# SSTuino_Evo.net
KiCad netlist of a schematic drawn in EAGLE
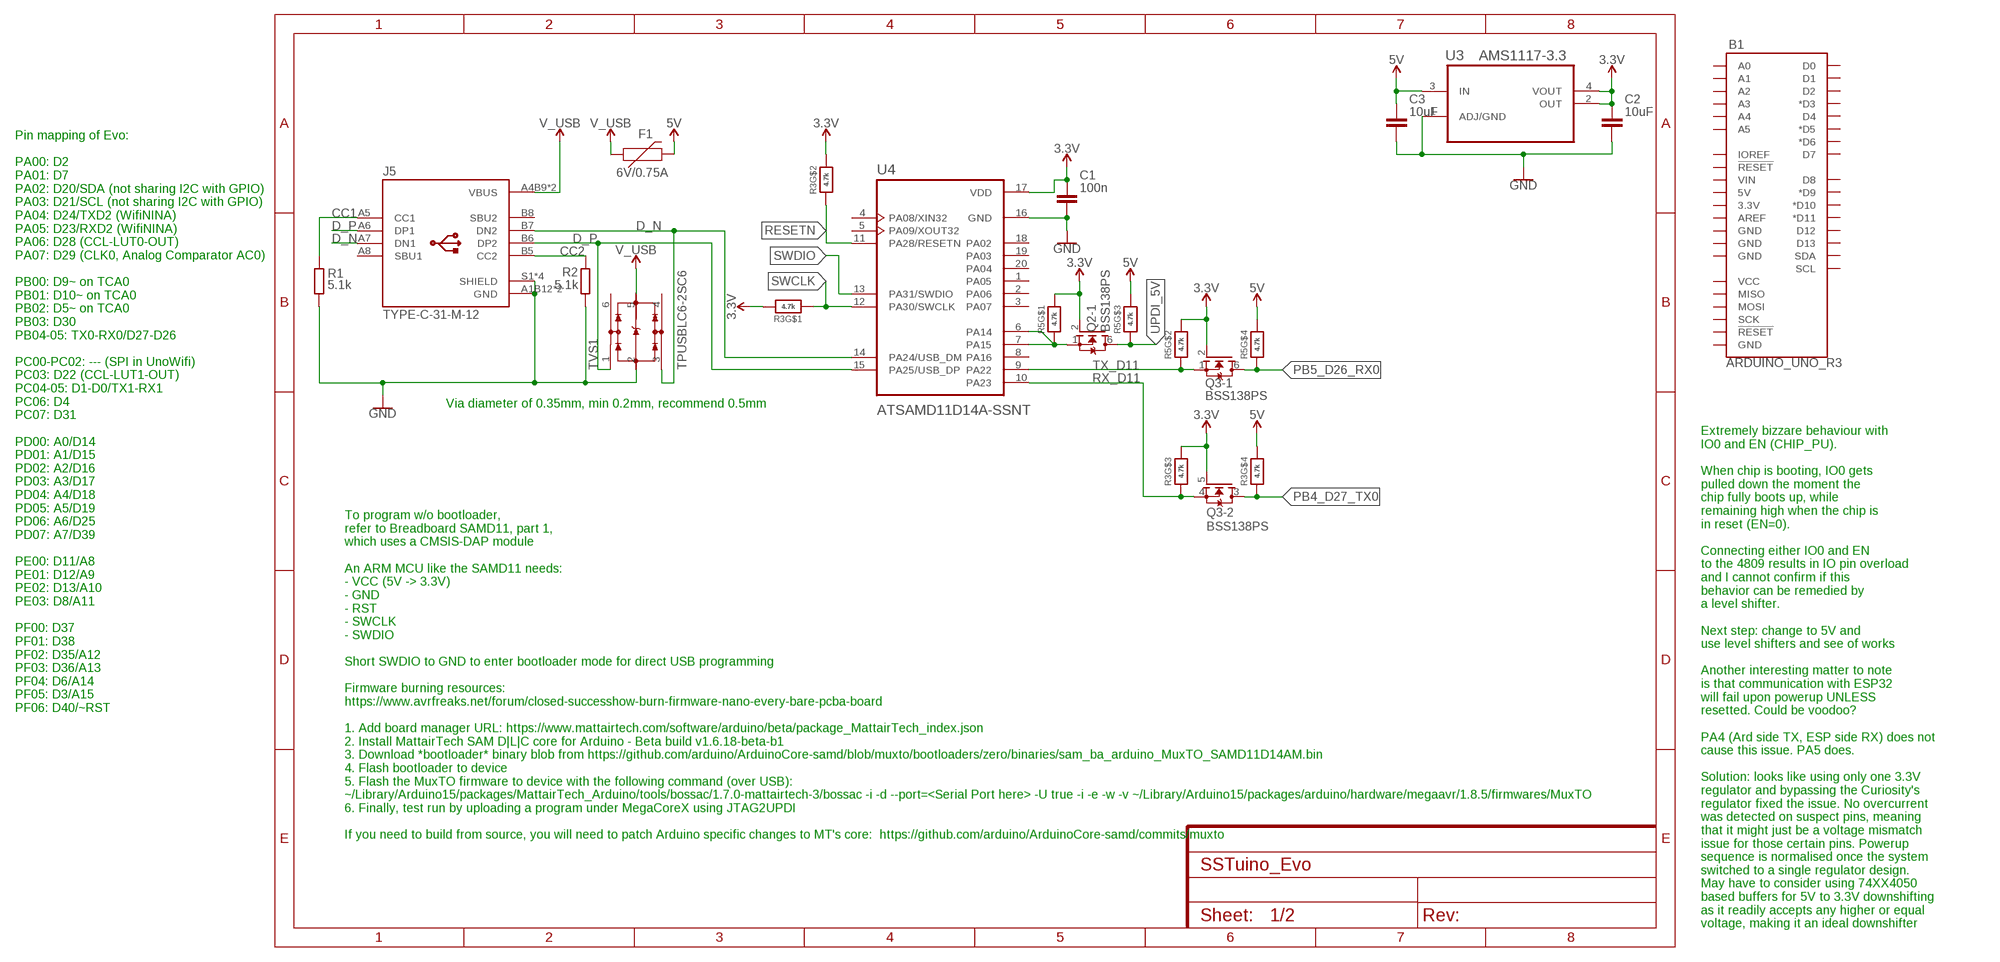
[diagram p0: schematic, sheet 1]
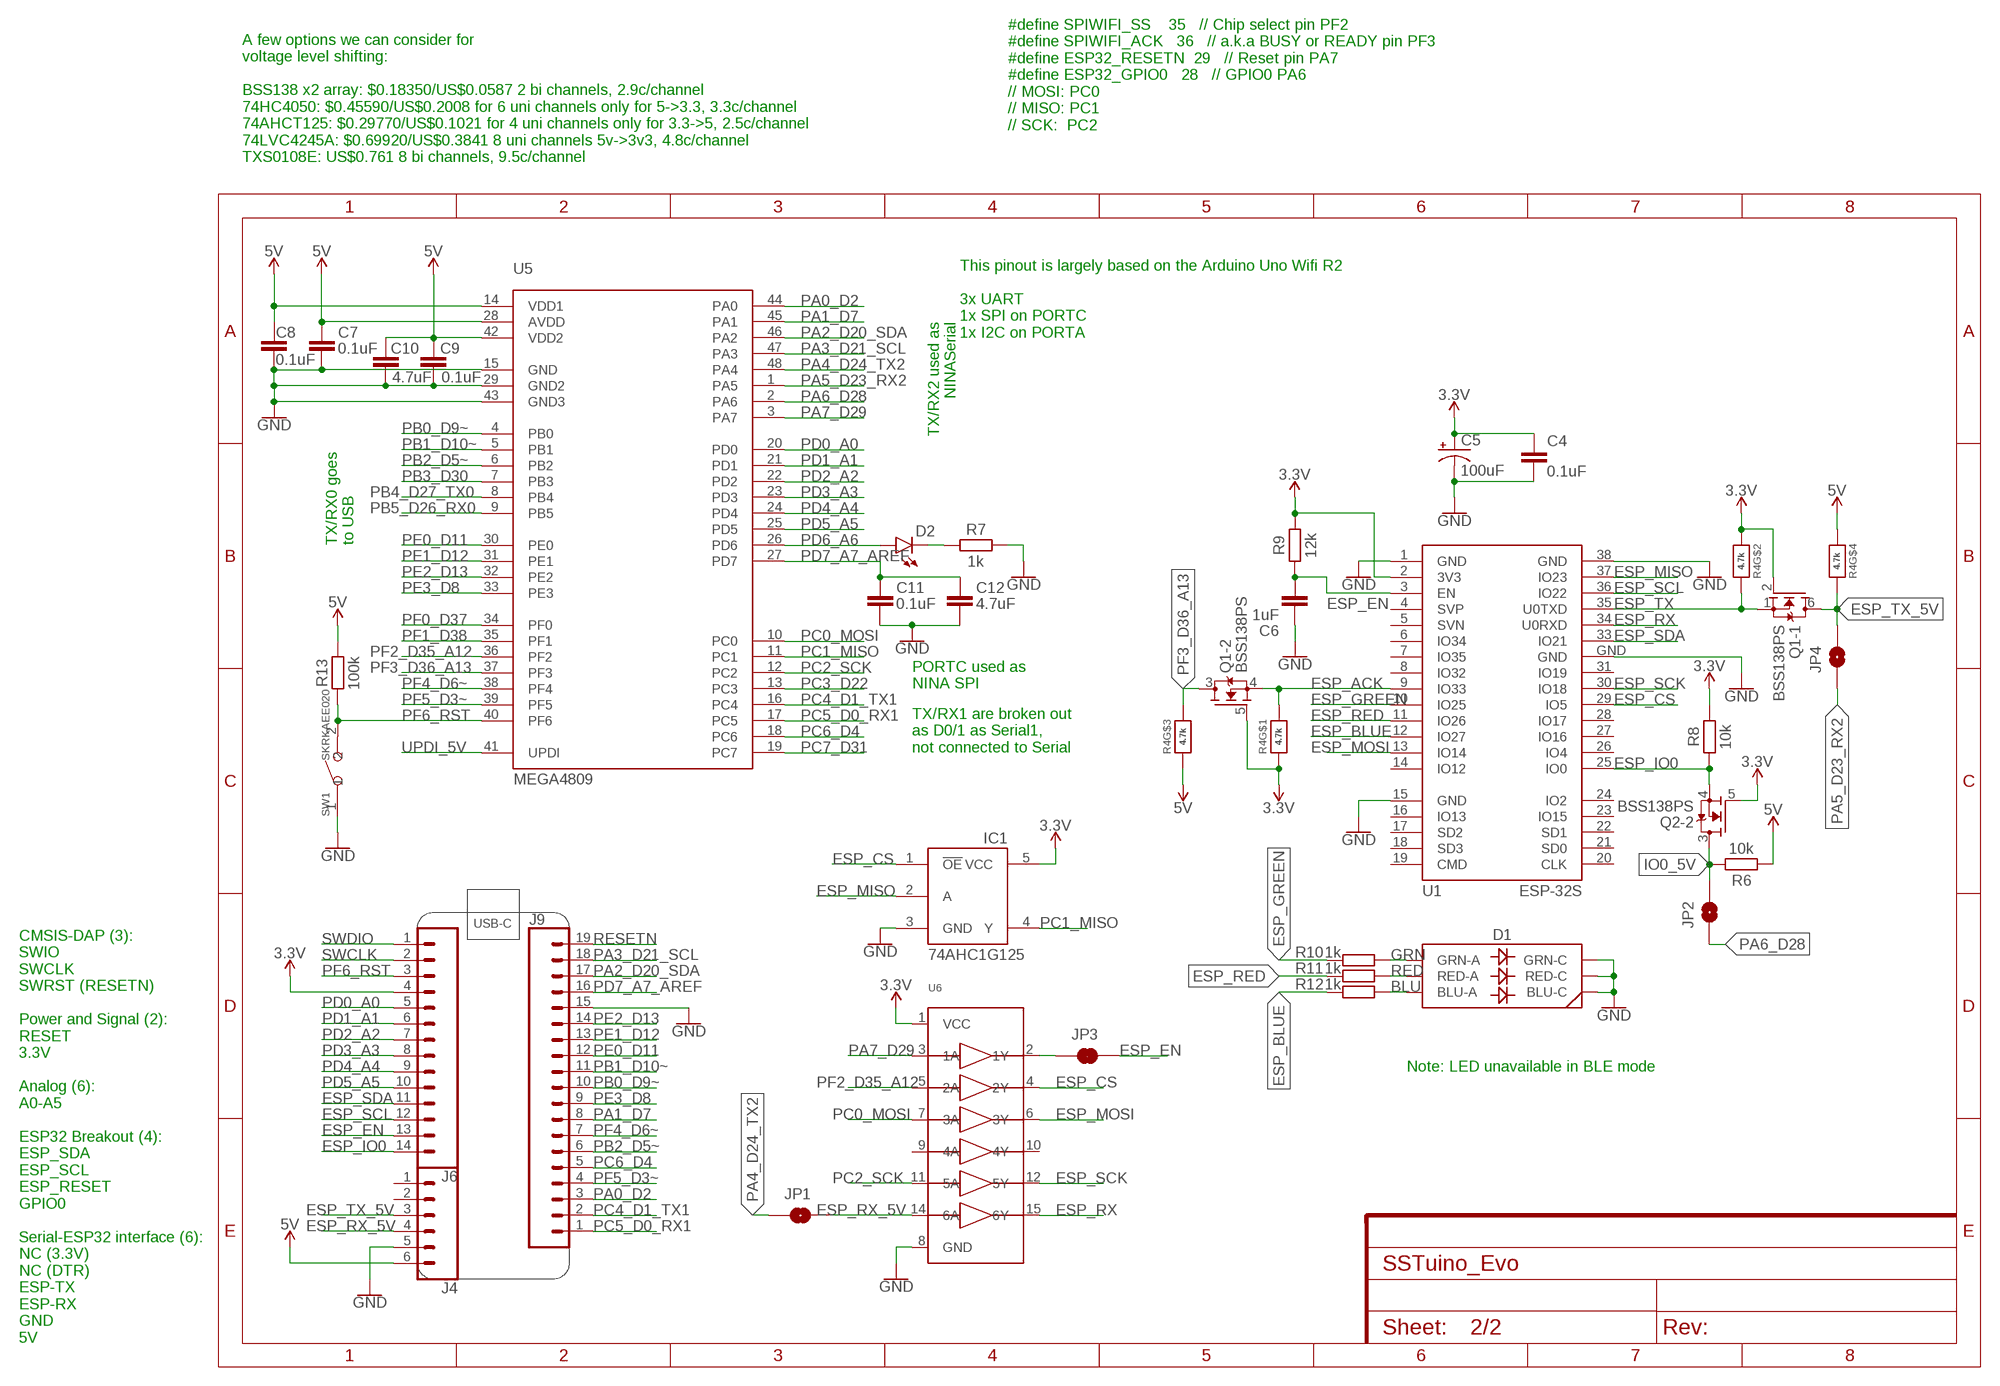
[diagram p1: schematic, sheet 2]

(export (version "E")
  (design (tool "Eeschema 10.0.6"))
  (components
    (comp (ref "C4")
      (value "0.1uF")
      (footprint "eagle-import:CAPC1005X60")
      (libsource (lib "eagle-import") (part "CCHIP-0402(1005-METRIC)_"))
    )
    (comp (ref "C5")
      (value "100uF")
      (footprint "eagle-import:CAPMP3216X180N")
      (libsource (lib "eagle-import") (part "C-POL-USTANTALUM-1206(3216-METRIC)_"))
    )
    (comp (ref "C6")
      (value "1uF")
      (footprint "eagle-import:CAPC1005X60")
      (libsource (lib "eagle-import") (part "CCHIP-0402(1005-METRIC)_"))
    )
    (comp (ref "C7")
      (value "0.1uF")
      (footprint "eagle-import:CAPC1005X60")
      (libsource (lib "eagle-import") (part "CCHIP-0402(1005-METRIC)_"))
    )
    (comp (ref "C8")
      (value "0.1uF")
      (footprint "eagle-import:CAPC1005X60")
      (libsource (lib "eagle-import") (part "CCHIP-0402(1005-METRIC)_"))
    )
    (comp (ref "C9")
      (value "0.1uF")
      (footprint "eagle-import:CAPC1005X60")
      (libsource (lib "eagle-import") (part "CCHIP-0402(1005-METRIC)_"))
    )
    (comp (ref "C10")
      (value "4.7uF")
      (footprint "eagle-import:CAPC1005X60")
      (libsource (lib "eagle-import") (part "CCHIP-0402(1005-METRIC)_"))
    )
    (comp (ref "C11")
      (value "0.1uF")
      (footprint "eagle-import:CAPC1005X60")
      (libsource (lib "eagle-import") (part "CCHIP-0402(1005-METRIC)_"))
    )
    (comp (ref "C12")
      (value "4.7uF")
      (footprint "eagle-import:CAPC1005X60")
      (libsource (lib "eagle-import") (part "CCHIP-0402(1005-METRIC)_"))
    )
    (comp (ref "D1")
      (value "LED-RGBTC5050RGBF08")
      (footprint "eagle-import:LED-TRICOLOR-5050")
      (libsource (lib "eagle-import") (part "LED-RGBTC5050RGBF08"))
    )
    (comp (ref "D2")
      (value "LED0603")
      (footprint "eagle-import:LED-0603")
      (libsource (lib "eagle-import") (part "LED0603"))
    )
    (comp (ref "IC1")
      (value "74AHC1G125")
      (footprint "eagle-import:SOT23-5L")
      (fields (field (name "LCSC_PART") "C124295"))
      (libsource (lib "eagle-import") (part "74AHC1G125"))
    )
    (comp (ref "J4")
      (value "CONN_06NO_SILK_FEMALE_PTH")
      (footprint "eagle-import:1X06_NO_SILK")
      (libsource (lib "eagle-import") (part "CONN_06NO_SILK_FEMALE_PTH"))
    )
    (comp (ref "J6")
      (value "CONN_14NO_SILK")
      (footprint "eagle-import:1X14_NO_SILK")
      (libsource (lib "eagle-import") (part "CONN_14NO_SILK"))
    )
    (comp (ref "J9")
      (value "CONN_191X19_NO_SILK")
      (footprint "eagle-import:1X19_NO_SILK")
      (libsource (lib "eagle-import") (part "CONN_191X19_NO_SILK"))
    )
    (comp (ref "JP1")
      (value "JUMPER-SMT_2_NO_SILK")
      (footprint "eagle-import:SMT-JUMPER_2_NO_SILK")
      (libsource (lib "eagle-import") (part "JUMPER-SMT_2_NO_SILK"))
    )
    (comp (ref "JP2")
      (value "JUMPER-SMT_2_NO_SILK")
      (footprint "eagle-import:SMT-JUMPER_2_NO_SILK")
      (libsource (lib "eagle-import") (part "JUMPER-SMT_2_NO_SILK"))
    )
    (comp (ref "JP3")
      (value "JUMPER-SMT_2_NC_TRACE_SILK")
      (footprint "eagle-import:SMT-JUMPER_2_NC_TRACE_SILK")
      (libsource (lib "eagle-import") (part "JUMPER-SMT_2_NC_TRACE_SILK"))
    )
    (comp (ref "JP4")
      (value "JUMPER-SMT_2_NO_SILK")
      (footprint "eagle-import:SMT-JUMPER_2_NO_SILK")
      (libsource (lib "eagle-import") (part "JUMPER-SMT_2_NO_SILK"))
    )
    (comp (ref "Q1")
      (value "BSS138PS")
      (footprint "eagle-import:ARDUINO-TRANSISTORS_SOT363")
      (fields (field (name "MANUFACTURER") "NXP") (field (name "LCSC_PART") "C193381"))
      (libsource (lib "eagle-import") (part "BSS138PS"))
    )
    (comp (ref "Q2")
      (value "BSS138PS")
      (footprint "eagle-import:ARDUINO-TRANSISTORS_SOT363")
      (fields (field (name "MANUFACTURER") "NXP") (field (name "LCSC_PART") "C193381"))
      (libsource (lib "eagle-import") (part "BSS138PS"))
    )
    (comp (ref "R4")
      (value "4.7k")
      (footprint "eagle-import:RESPACK_4X0402")
      (fields (field (name "LCSC_PART") "C1980"))
      (libsource (lib "eagle-import") (part "RESISTOR_4PACK0402"))
    )
    (comp (ref "R6")
      (value "10k")
      (footprint "eagle-import:RESC1005X40")
      (libsource (lib "eagle-import") (part "RCHIP-0402(1005-METRIC)_"))
    )
    (comp (ref "R7")
      (value "1k")
      (footprint "eagle-import:RESC1005X40")
      (libsource (lib "eagle-import") (part "RCHIP-0402(1005-METRIC)_"))
    )
    (comp (ref "R8")
      (value "10k")
      (footprint "eagle-import:RESC1005X40")
      (libsource (lib "eagle-import") (part "RCHIP-0402(1005-METRIC)_"))
    )
    (comp (ref "R9")
      (value "12k")
      (footprint "eagle-import:RESC1005X40")
      (libsource (lib "eagle-import") (part "RCHIP-0402(1005-METRIC)_"))
    )
    (comp (ref "R10")
      (value "1k")
      (footprint "eagle-import:RESC1005X40")
      (libsource (lib "eagle-import") (part "RCHIP-0402(1005-METRIC)_"))
    )
    (comp (ref "R11")
      (value "1k")
      (footprint "eagle-import:RESC1005X40")
      (libsource (lib "eagle-import") (part "RCHIP-0402(1005-METRIC)_"))
    )
    (comp (ref "R12")
      (value "1k")
      (footprint "eagle-import:RESC1005X40")
      (libsource (lib "eagle-import") (part "RCHIP-0402(1005-METRIC)_"))
    )
    (comp (ref "R13")
      (value "100k")
      (footprint "eagle-import:RESC1005X40")
      (libsource (lib "eagle-import") (part "RCHIP-0402(1005-METRIC)_"))
    )
    (comp (ref "SW1")
      (value "SKRKAEE020")
      (footprint "eagle-import:SW2-2.6-3.9X2.9X1.5+0.4MM")
      (fields (field (name "LCSC_PART") "C115357") (field (name "LCSC_PART_1") "C115357"))
      (libsource (lib "eagle-import") (part "SMD-BUTTON(2P-3.9X2.9X1.5+0.4MM)-SKRKAEE020"))
    )
    (comp (ref "U1")
      (value "ESP-32S")
      (footprint "eagle-import:ESP-32S")
      (libsource (lib "eagle-import") (part "ESP-32S"))
    )
    (comp (ref "U5")
      (value "MEGA4809")
      (footprint "eagle-import:TQFP48")
      (fields (field (name "LCSC_PART") "C189475"))
      (libsource (lib "eagle-import") (part "MEGA4809"))
    )
    (comp (ref "U6")
      (value "74HC4050DTSSOP")
      (footprint "eagle-import:TSSOP16")
      (fields (field (name "LCSC_PART") "C43181"))
      (libsource (lib "eagle-import") (part "74HC4050DTSSOP"))
    )
    (comp (ref "B1")
      (value "ARDUINO_UNO_R3")
      (footprint "eagle-import:ARDUINO_R3")
      (libsource (lib "eagle-import") (part "ARDUINO_UNO_R3"))
    )
    (comp (ref "C1")
      (value "100n")
      (footprint "eagle-import:CAPC1005X60")
      (libsource (lib "eagle-import") (part "CCHIP-0402(1005-METRIC)_"))
    )
    (comp (ref "C2")
      (value "10uF")
      (footprint "eagle-import:CAPC1608X85")
      (libsource (lib "eagle-import") (part "CCHIP-0603(1608-METRIC)_"))
    )
    (comp (ref "C3")
      (value "10uF")
      (footprint "eagle-import:CAPC1608X85")
      (libsource (lib "eagle-import") (part "CCHIP-0603(1608-METRIC)_"))
    )
    (comp (ref "F1")
      (value "6V/0.75A")
      (footprint "eagle-import:1206")
      (fields (field (name "LCSC_PART") "C99563"))
      (libsource (lib "eagle-import") (part "PPTC_THREE-QUARTER-AMP"))
    )
    (comp (ref "J5")
      (value "TYPE-C-31-M-12")
      (footprint "eagle-import:HRO_TYPE-C-31-M-12")
      (fields (field (name "MF") "HRO Electronics Co., Ltd.") (field (name "LCSC_PART") "C165948"))
      (libsource (lib "eagle-import") (part "TYPE-C-31-M-12"))
    )
    (comp (ref "Q3")
      (value "BSS138PS")
      (footprint "eagle-import:ARDUINO-TRANSISTORS_SOT363")
      (fields (field (name "MANUFACTURER") "NXP") (field (name "LCSC_PART") "C193381"))
      (libsource (lib "eagle-import") (part "BSS138PS"))
    )
    (comp (ref "R1")
      (value "5.1k")
      (footprint "eagle-import:RESC1005X40")
      (libsource (lib "eagle-import") (part "RCHIP-0402(1005-METRIC)_"))
    )
    (comp (ref "R2")
      (value "5.1k")
      (footprint "eagle-import:RESC1005X40")
      (libsource (lib "eagle-import") (part "RCHIP-0402(1005-METRIC)_"))
    )
    (comp (ref "R3")
      (value "4.7k")
      (footprint "eagle-import:RESPACK_4X0402")
      (fields (field (name "LCSC_PART") "C1980"))
      (libsource (lib "eagle-import") (part "RESISTOR_4PACK0402"))
    )
    (comp (ref "R5")
      (value "4.7k")
      (footprint "eagle-import:RESPACK_4X0402")
      (fields (field (name "LCSC_PART") "C1980"))
      (libsource (lib "eagle-import") (part "RESISTOR_4PACK0402"))
    )
    (comp (ref "TVS1")
      (value "TPUSBLC6-2SC6")
      (footprint "eagle-import:SOT95P280X110-6N")
      (fields (field (name "LCSC_PART") "C558442"))
      (libsource (lib "eagle-import") (part "TPUSBLC6-2SC6"))
    )
    (comp (ref "U3")
      (value "AMS1117-3.3")
      (footprint "eagle-import:SOT230P696X180-4N")
      (fields (field (name "MPN") "LM1117MP-3.3") (field (name "LCSC_PART") "C6186"))
      (libsource (lib "eagle-import") (part "LM1117MP-3.3"))
    )
    (comp (ref "U4")
      (value "ATSAMD11D14A-SSNT")
      (footprint "eagle-import:SOIC127P1030X265-20N")
      (fields (field (name "MF") "Microchip") (field (name "LCSC_PART") "C2053599"))
      (libsource (lib "eagle-import") (part "ATSAMD11D14A-SSNT"))
    )
  )
  (nets
    (net (code "1") (name "3.3V") (class "Default")
      (node (ref "C1") (pin "1") (pinfunction "1_1") (pintype "passive"))
      (node (ref "C2") (pin "1") (pinfunction "1_1") (pintype "passive"))
      (node (ref "C4") (pin "1") (pinfunction "1_1") (pintype "passive"))
      (node (ref "C5") (pin "1") (pinfunction "+_1") (pintype "passive"))
      (node (ref "IC1") (pin "5") (pinfunction "VCC_5") (pintype "power_in"))
      (node (ref "J6") (pin "4") (pinfunction "4_4") (pintype "passive"))
      (node (ref "Q1") (pin "2") (pinfunction "G_2") (pintype "passive"))
      (node (ref "Q1") (pin "5") (pinfunction "G_5") (pintype "passive"))
      (node (ref "Q2") (pin "2") (pinfunction "G_2") (pintype "passive"))
      (node (ref "Q2") (pin "5") (pinfunction "G_5") (pintype "passive"))
      (node (ref "Q3") (pin "2") (pinfunction "G_2") (pintype "passive"))
      (node (ref "Q3") (pin "5") (pinfunction "G_5") (pintype "passive"))
      (node (ref "R3") (pin "6") (pinfunction "2_6") (pintype "passive"))
      (node (ref "R3") (pin "7") (pinfunction "2_7") (pintype "passive"))
      (node (ref "R3") (pin "8") (pinfunction "2_8") (pintype "passive"))
      (node (ref "R4") (pin "1") (pinfunction "1_1") (pintype "passive"))
      (node (ref "R4") (pin "2") (pinfunction "1_2") (pintype "passive"))
      (node (ref "R5") (pin "7") (pinfunction "2_7") (pintype "passive"))
      (node (ref "R5") (pin "8") (pinfunction "2_8") (pintype "passive"))
      (node (ref "R8") (pin "2") (pinfunction "2_2") (pintype "passive"))
      (node (ref "R9") (pin "2") (pinfunction "2_2") (pintype "passive"))
      (node (ref "U1") (pin "2") (pinfunction "3V3_2") (pintype "power_in"))
      (node (ref "U3") (pin "2") (pinfunction "OUT_2") (pintype "output"))
      (node (ref "U3") (pin "4") (pinfunction "VOUT_4") (pintype "output"))
      (node (ref "U4") (pin "17") (pinfunction "VDD_17") (pintype "power_in"))
      (node (ref "U6") (pin "1") (pinfunction "VCC_1") (pintype "bidirectional"))
    )
    (net (code "2") (name "5V") (class "Default")
      (node (ref "C10") (pin "1") (pinfunction "1_1") (pintype "passive"))
      (node (ref "C3") (pin "1") (pinfunction "1_1") (pintype "passive"))
      (node (ref "C7") (pin "1") (pinfunction "1_1") (pintype "passive"))
      (node (ref "C8") (pin "1") (pinfunction "1_1") (pintype "passive"))
      (node (ref "C9") (pin "1") (pinfunction "1_1") (pintype "passive"))
      (node (ref "F1") (pin "2") (pinfunction "2_2") (pintype "bidirectional"))
      (node (ref "J4") (pin "6") (pinfunction "6_6") (pintype "passive"))
      (node (ref "R13") (pin "2") (pinfunction "2_2") (pintype "passive"))
      (node (ref "R3") (pin "5") (pinfunction "2_5") (pintype "passive"))
      (node (ref "R4") (pin "3") (pinfunction "1_3") (pintype "passive"))
      (node (ref "R4") (pin "4") (pinfunction "1_4") (pintype "passive"))
      (node (ref "R5") (pin "5") (pinfunction "2_5") (pintype "passive"))
      (node (ref "R5") (pin "6") (pinfunction "2_6") (pintype "passive"))
      (node (ref "R6") (pin "1") (pinfunction "1_1") (pintype "passive"))
      (node (ref "U3") (pin "3") (pinfunction "IN_3") (pintype "input"))
      (node (ref "U5") (pin "14") (pinfunction "VDD1_14") (pintype "bidirectional"))
      (node (ref "U5") (pin "28") (pinfunction "AVDD_28") (pintype "bidirectional"))
      (node (ref "U5") (pin "42") (pinfunction "VDD2_42") (pintype "bidirectional"))
    )
    (net (code "3") (name "BLU") (class "Default")
      (node (ref "D1") (pin "6") (pinfunction "BLU-A_6") (pintype "bidirectional"))
      (node (ref "R12") (pin "2") (pinfunction "2_2") (pintype "passive"))
    )
    (net (code "4") (name "CC1") (class "Default")
      (node (ref "J5") (pin "A5") (pinfunction "CC1_A5") (pintype "bidirectional"))
      (node (ref "R1") (pin "1") (pinfunction "1_1") (pintype "passive"))
    )
    (net (code "5") (name "CC2") (class "Default")
      (node (ref "J5") (pin "B5") (pinfunction "CC2_B5") (pintype "bidirectional"))
      (node (ref "R2") (pin "2") (pinfunction "2_2") (pintype "passive"))
    )
    (net (code "6") (name "D_N") (class "Default")
      (node (ref "J5") (pin "A7") (pinfunction "DN1_A7") (pintype "bidirectional"))
      (node (ref "J5") (pin "B7") (pinfunction "DN2_B7") (pintype "bidirectional"))
      (node (ref "TVS1") (pin "3") (pinfunction "IO2_3") (pintype "passive"))
      (node (ref "U4") (pin "14") (pinfunction "PA24/USB_DM_14") (pintype "bidirectional"))
    )
    (net (code "7") (name "D_P") (class "Default")
      (node (ref "J5") (pin "A6") (pinfunction "DP1_A6") (pintype "bidirectional"))
      (node (ref "J5") (pin "B6") (pinfunction "DP2_B6") (pintype "bidirectional"))
      (node (ref "TVS1") (pin "1") (pinfunction "IO1_1") (pintype "passive"))
      (node (ref "U4") (pin "15") (pinfunction "PA25/USB_DP_15") (pintype "bidirectional"))
    )
    (net (code "8") (name "ESP_ACK") (class "Default")
      (node (ref "Q1") (pin "4") (pinfunction "S_4") (pintype "passive"))
      (node (ref "R4") (pin "8") (pinfunction "2_8") (pintype "passive"))
      (node (ref "U1") (pin "9") (pinfunction "IO33_9") (pintype "bidirectional"))
    )
    (net (code "9") (name "ESP_BLUE") (class "Default")
      (node (ref "R12") (pin "1") (pinfunction "1_1") (pintype "passive"))
      (node (ref "U1") (pin "12") (pinfunction "IO27_12") (pintype "bidirectional"))
    )
    (net (code "10") (name "ESP_CS") (class "Default")
      (node (ref "IC1") (pin "1") (pinfunction "~{OE}_1") (pintype "input"))
      (node (ref "U1") (pin "29") (pinfunction "IO5_29") (pintype "bidirectional"))
      (node (ref "U6") (pin "4") (pinfunction "2Y_4") (pintype "bidirectional"))
    )
    (net (code "11") (name "ESP_EN") (class "Default")
      (node (ref "C6") (pin "2") (pinfunction "2_2") (pintype "passive"))
      (node (ref "J6") (pin "13") (pinfunction "13_13") (pintype "passive"))
      (node (ref "JP3") (pin "2") (pinfunction "2_2") (pintype "passive"))
      (node (ref "R9") (pin "1") (pinfunction "1_1") (pintype "passive"))
      (node (ref "U1") (pin "3") (pinfunction "EN_3") (pintype "input"))
    )
    (net (code "12") (name "ESP_GREEN") (class "Default")
      (node (ref "R10") (pin "1") (pinfunction "1_1") (pintype "passive"))
      (node (ref "U1") (pin "10") (pinfunction "IO25_10") (pintype "bidirectional"))
    )
    (net (code "13") (name "ESP_IO0") (class "Default")
      (node (ref "J6") (pin "14") (pinfunction "14_14") (pintype "passive"))
      (node (ref "Q2") (pin "4") (pinfunction "S_4") (pintype "passive"))
      (node (ref "R8") (pin "1") (pinfunction "1_1") (pintype "passive"))
      (node (ref "U1") (pin "25") (pinfunction "IO0_25") (pintype "bidirectional"))
    )
    (net (code "14") (name "ESP_MISO") (class "Default")
      (node (ref "IC1") (pin "2") (pinfunction "A_2") (pintype "input"))
      (node (ref "U1") (pin "37") (pinfunction "IO23_37") (pintype "bidirectional"))
    )
    (net (code "15") (name "ESP_MOSI") (class "Default")
      (node (ref "U1") (pin "13") (pinfunction "IO14_13") (pintype "bidirectional"))
      (node (ref "U6") (pin "6") (pinfunction "3Y_6") (pintype "bidirectional"))
    )
    (net (code "16") (name "ESP_RED") (class "Default")
      (node (ref "R11") (pin "1") (pinfunction "1_1") (pintype "passive"))
      (node (ref "U1") (pin "11") (pinfunction "IO26_11") (pintype "bidirectional"))
    )
    (net (code "17") (name "ESP_RX") (class "Default")
      (node (ref "U1") (pin "34") (pinfunction "U0RXD_34") (pintype "bidirectional"))
      (node (ref "U6") (pin "15") (pinfunction "6Y_15") (pintype "bidirectional"))
    )
    (net (code "18") (name "ESP_RX_5V") (class "Default")
      (node (ref "J4") (pin "4") (pinfunction "4_4") (pintype "passive"))
      (node (ref "JP1") (pin "2") (pinfunction "2_2") (pintype "passive"))
      (node (ref "U6") (pin "14") (pinfunction "6A_14") (pintype "bidirectional"))
    )
    (net (code "19") (name "ESP_SCK") (class "Default")
      (node (ref "U1") (pin "30") (pinfunction "IO18_30") (pintype "bidirectional"))
      (node (ref "U6") (pin "12") (pinfunction "5Y_12") (pintype "bidirectional"))
    )
    (net (code "20") (name "ESP_SCL") (class "Default")
      (node (ref "J6") (pin "12") (pinfunction "12_12") (pintype "passive"))
      (node (ref "U1") (pin "36") (pinfunction "IO22_36") (pintype "bidirectional"))
    )
    (net (code "21") (name "ESP_SDA") (class "Default")
      (node (ref "J6") (pin "11") (pinfunction "11_11") (pintype "passive"))
      (node (ref "U1") (pin "33") (pinfunction "IO21_33") (pintype "bidirectional"))
    )
    (net (code "22") (name "ESP_TX") (class "Default")
      (node (ref "Q1") (pin "1") (pinfunction "S_1") (pintype "passive"))
      (node (ref "R4") (pin "7") (pinfunction "2_7") (pintype "passive"))
      (node (ref "U1") (pin "35") (pinfunction "U0TXD_35") (pintype "bidirectional"))
    )
    (net (code "23") (name "ESP_TX_5V") (class "Default")
      (node (ref "J4") (pin "3") (pinfunction "3_3") (pintype "passive"))
      (node (ref "JP4") (pin "2") (pinfunction "2_2") (pintype "passive"))
      (node (ref "Q1") (pin "6") (pinfunction "D_6") (pintype "passive"))
      (node (ref "R4") (pin "5") (pinfunction "2_5") (pintype "passive"))
    )
    (net (code "24") (name "GND") (class "Default")
      (node (ref "C1") (pin "2") (pinfunction "2_2") (pintype "passive"))
      (node (ref "C10") (pin "2") (pinfunction "2_2") (pintype "passive"))
      (node (ref "C11") (pin "2") (pinfunction "2_2") (pintype "passive"))
      (node (ref "C12") (pin "2") (pinfunction "2_2") (pintype "passive"))
      (node (ref "C2") (pin "2") (pinfunction "2_2") (pintype "passive"))
      (node (ref "C3") (pin "2") (pinfunction "2_2") (pintype "passive"))
      (node (ref "C4") (pin "2") (pinfunction "2_2") (pintype "passive"))
      (node (ref "C5") (pin "2") (pinfunction "-_2") (pintype "passive"))
      (node (ref "C6") (pin "1") (pinfunction "1_1") (pintype "passive"))
      (node (ref "C7") (pin "2") (pinfunction "2_2") (pintype "passive"))
      (node (ref "C8") (pin "2") (pinfunction "2_2") (pintype "passive"))
      (node (ref "C9") (pin "2") (pinfunction "2_2") (pintype "passive"))
      (node (ref "D1") (pin "1") (pinfunction "BLU-C_1") (pintype "bidirectional"))
      (node (ref "D1") (pin "2") (pinfunction "RED-C_2") (pintype "bidirectional"))
      (node (ref "D1") (pin "3") (pinfunction "GRN-C_3") (pintype "bidirectional"))
      (node (ref "IC1") (pin "3") (pinfunction "GND_3") (pintype "power_in"))
      (node (ref "J4") (pin "5") (pinfunction "5_5") (pintype "passive"))
      (node (ref "J5") (pin "A1B12") (pinfunction "GND_A1B12") (pintype "power_in"))
      (node (ref "J5") (pin "B1A12") (pinfunction "GND_B1A12") (pintype "power_in"))
      (node (ref "J5") (pin "S1") (pinfunction "SHIELD_S1") (pintype "passive"))
      (node (ref "J5") (pin "S2") (pinfunction "SHIELD_S2") (pintype "passive"))
      (node (ref "J5") (pin "S3") (pinfunction "SHIELD_S3") (pintype "passive"))
      (node (ref "J5") (pin "S4") (pinfunction "SHIELD_S4") (pintype "passive"))
      (node (ref "J9") (pin "15") (pinfunction "15_15") (pintype "passive"))
      (node (ref "R1") (pin "2") (pinfunction "2_2") (pintype "passive"))
      (node (ref "R2") (pin "1") (pinfunction "1_1") (pintype "passive"))
      (node (ref "R7") (pin "2") (pinfunction "2_2") (pintype "passive"))
      (node (ref "SW1") (pin "1") (pinfunction "1_1") (pintype "bidirectional"))
      (node (ref "TVS1") (pin "2") (pinfunction "VSS_2") (pintype "power_in"))
      (node (ref "U1") (pin "1") (pinfunction "GND_1") (pintype "power_in"))
      (node (ref "U1") (pin "15") (pinfunction "GND_15") (pintype "power_in"))
      (node (ref "U1") (pin "38") (pinfunction "GND_38") (pintype "power_in"))
      (node (ref "U1") (pin "GND") (pinfunction "GND_GND") (pintype "power_in"))
      (node (ref "U3") (pin "1") (pinfunction "ADJ/GND_1") (pintype "passive"))
      (node (ref "U4") (pin "16") (pinfunction "GND_16") (pintype "power_in"))
      (node (ref "U5") (pin "15") (pinfunction "GND_15") (pintype "bidirectional"))
      (node (ref "U5") (pin "29") (pinfunction "GND2_29") (pintype "bidirectional"))
      (node (ref "U5") (pin "43") (pinfunction "GND3_43") (pintype "bidirectional"))
      (node (ref "U6") (pin "8") (pinfunction "GND_8") (pintype "bidirectional"))
    )
    (net (code "25") (name "GRN") (class "Default")
      (node (ref "D1") (pin "4") (pinfunction "GRN-A_4") (pintype "bidirectional"))
      (node (ref "R10") (pin "2") (pinfunction "2_2") (pintype "passive"))
    )
    (net (code "26") (name "IO0_5V") (class "Default")
      (node (ref "JP2") (pin "2") (pinfunction "2_2") (pintype "passive"))
      (node (ref "Q2") (pin "3") (pinfunction "D_3") (pintype "passive"))
      (node (ref "R6") (pin "2") (pinfunction "2_2") (pintype "passive"))
    )
    (net (code "27") (name "Net-(D2-PadC)") (class "Default")
      (node (ref "D2") (pin "C") (pinfunction "C_C") (pintype "passive"))
      (node (ref "R7") (pin "1") (pinfunction "1_1") (pintype "passive"))
    )
    (net (code "28") (name "Net-(Q2A-S)") (class "Default")
      (node (ref "Q2") (pin "1") (pinfunction "S_1") (pintype "passive"))
      (node (ref "R5") (pin "1") (pinfunction "1_1") (pintype "passive"))
      (node (ref "U4") (pin "6") (pinfunction "PA14_6") (pintype "bidirectional"))
      (node (ref "U4") (pin "7") (pinfunction "PA15_7") (pintype "bidirectional"))
    )
    (net (code "29") (name "Net-(U6-1Y)") (class "Default")
      (node (ref "JP3") (pin "1") (pinfunction "1_1") (pintype "passive"))
      (node (ref "U6") (pin "2") (pinfunction "1Y_2") (pintype "bidirectional"))
    )
    (net (code "30") (name "PA0_D2") (class "Default")
      (node (ref "J9") (pin "3") (pinfunction "3_3") (pintype "passive"))
      (node (ref "U5") (pin "44") (pinfunction "PA0_44") (pintype "bidirectional"))
    )
    (net (code "31") (name "PA1_D7") (class "Default")
      (node (ref "J9") (pin "8") (pinfunction "8_8") (pintype "passive"))
      (node (ref "U5") (pin "45") (pinfunction "PA1_45") (pintype "bidirectional"))
    )
    (net (code "32") (name "PA2_D20_SDA") (class "Default")
      (node (ref "J9") (pin "17") (pinfunction "17_17") (pintype "passive"))
      (node (ref "U5") (pin "46") (pinfunction "PA2_46") (pintype "bidirectional"))
    )
    (net (code "33") (name "PA3_D21_SCL") (class "Default")
      (node (ref "J9") (pin "18") (pinfunction "18_18") (pintype "passive"))
      (node (ref "U5") (pin "47") (pinfunction "PA3_47") (pintype "bidirectional"))
    )
    (net (code "34") (name "PA4_D24_TX2") (class "Default")
      (node (ref "JP1") (pin "1") (pinfunction "1_1") (pintype "passive"))
      (node (ref "U5") (pin "48") (pinfunction "PA4_48") (pintype "bidirectional"))
    )
    (net (code "35") (name "PA5_D23_RX2") (class "Default")
      (node (ref "JP4") (pin "1") (pinfunction "1_1") (pintype "passive"))
      (node (ref "U5") (pin "1") (pinfunction "PA5_1") (pintype "bidirectional"))
    )
    (net (code "36") (name "PA6_D28") (class "Default")
      (node (ref "JP2") (pin "1") (pinfunction "1_1") (pintype "passive"))
      (node (ref "U5") (pin "2") (pinfunction "PA6_2") (pintype "bidirectional"))
    )
    (net (code "37") (name "PA7_D29") (class "Default")
      (node (ref "U5") (pin "3") (pinfunction "PA7_3") (pintype "bidirectional"))
      (node (ref "U6") (pin "3") (pinfunction "1A_3") (pintype "bidirectional"))
    )
    (net (code "38") (name "PB0_D9~{}") (class "Default")
      (node (ref "J9") (pin "10") (pinfunction "10_10") (pintype "passive"))
      (node (ref "U5") (pin "4") (pinfunction "PB0_4") (pintype "bidirectional"))
    )
    (net (code "39") (name "PB1_D10~{}") (class "Default")
      (node (ref "J9") (pin "11") (pinfunction "11_11") (pintype "passive"))
      (node (ref "U5") (pin "5") (pinfunction "PB1_5") (pintype "bidirectional"))
    )
    (net (code "40") (name "PB2_D5~{}") (class "Default")
      (node (ref "J9") (pin "6") (pinfunction "6_6") (pintype "passive"))
      (node (ref "U5") (pin "6") (pinfunction "PB2_6") (pintype "bidirectional"))
    )
    (net (code "41") (name "PB3_D30") (class "Default")
      (node (ref "U5") (pin "7") (pinfunction "PB3_7") (pintype "bidirectional"))
    )
    (net (code "42") (name "PB4_D27_TX0") (class "Default")
      (node (ref "Q3") (pin "3") (pinfunction "D_3") (pintype "passive"))
      (node (ref "R3") (pin "4") (pinfunction "1_4") (pintype "passive"))
      (node (ref "U5") (pin "8") (pinfunction "PB4_8") (pintype "bidirectional"))
    )
    (net (code "43") (name "PB5_D26_RX0") (class "Default")
      (node (ref "Q3") (pin "6") (pinfunction "D_6") (pintype "passive"))
      (node (ref "R5") (pin "4") (pinfunction "1_4") (pintype "passive"))
      (node (ref "U5") (pin "9") (pinfunction "PB5_9") (pintype "bidirectional"))
    )
    (net (code "44") (name "PC0_MOSI") (class "Default")
      (node (ref "U5") (pin "10") (pinfunction "PC0_10") (pintype "bidirectional"))
      (node (ref "U6") (pin "7") (pinfunction "3A_7") (pintype "bidirectional"))
    )
    (net (code "45") (name "PC1_MISO") (class "Default")
      (node (ref "IC1") (pin "4") (pinfunction "Y_4") (pintype "output"))
      (node (ref "U5") (pin "11") (pinfunction "PC1_11") (pintype "bidirectional"))
    )
    (net (code "46") (name "PC2_SCK") (class "Default")
      (node (ref "U5") (pin "12") (pinfunction "PC2_12") (pintype "bidirectional"))
      (node (ref "U6") (pin "11") (pinfunction "5A_11") (pintype "bidirectional"))
    )
    (net (code "47") (name "PC3_D22") (class "Default")
      (node (ref "U5") (pin "13") (pinfunction "PC3_13") (pintype "bidirectional"))
    )
    (net (code "48") (name "PC4_D1_TX1") (class "Default")
      (node (ref "J9") (pin "2") (pinfunction "2_2") (pintype "passive"))
      (node (ref "U5") (pin "16") (pinfunction "PC4_16") (pintype "bidirectional"))
    )
    (net (code "49") (name "PC5_D0_RX1") (class "Default")
      (node (ref "J9") (pin "1") (pinfunction "1_1") (pintype "passive"))
      (node (ref "U5") (pin "17") (pinfunction "PC5_17") (pintype "bidirectional"))
    )
    (net (code "50") (name "PC6_D4") (class "Default")
      (node (ref "J9") (pin "5") (pinfunction "5_5") (pintype "passive"))
      (node (ref "U5") (pin "18") (pinfunction "PC6_18") (pintype "bidirectional"))
    )
    (net (code "51") (name "PC7_D31") (class "Default")
      (node (ref "U5") (pin "19") (pinfunction "PC7_19") (pintype "bidirectional"))
    )
    (net (code "52") (name "PD0_A0") (class "Default")
      (node (ref "J6") (pin "5") (pinfunction "5_5") (pintype "passive"))
      (node (ref "U5") (pin "20") (pinfunction "PD0_20") (pintype "bidirectional"))
    )
    (net (code "53") (name "PD1_A1") (class "Default")
      (node (ref "J6") (pin "6") (pinfunction "6_6") (pintype "passive"))
      (node (ref "U5") (pin "21") (pinfunction "PD1_21") (pintype "bidirectional"))
    )
    (net (code "54") (name "PD2_A2") (class "Default")
      (node (ref "J6") (pin "7") (pinfunction "7_7") (pintype "passive"))
      (node (ref "U5") (pin "22") (pinfunction "PD2_22") (pintype "bidirectional"))
    )
    (net (code "55") (name "PD3_A3") (class "Default")
      (node (ref "J6") (pin "8") (pinfunction "8_8") (pintype "passive"))
      (node (ref "U5") (pin "23") (pinfunction "PD3_23") (pintype "bidirectional"))
    )
    (net (code "56") (name "PD4_A4") (class "Default")
      (node (ref "J6") (pin "9") (pinfunction "9_9") (pintype "passive"))
      (node (ref "U5") (pin "24") (pinfunction "PD4_24") (pintype "bidirectional"))
    )
    (net (code "57") (name "PD5_A5") (class "Default")
      (node (ref "J6") (pin "10") (pinfunction "10_10") (pintype "passive"))
      (node (ref "U5") (pin "25") (pinfunction "PD5_25") (pintype "bidirectional"))
    )
    (net (code "58") (name "PD6_A6") (class "Default")
      (node (ref "D2") (pin "A") (pinfunction "A_A") (pintype "passive"))
      (node (ref "U5") (pin "26") (pinfunction "PD6_26") (pintype "bidirectional"))
    )
    (net (code "59") (name "PD7_A7_AREF") (class "Default")
      (node (ref "C11") (pin "1") (pinfunction "1_1") (pintype "passive"))
      (node (ref "C12") (pin "1") (pinfunction "1_1") (pintype "passive"))
      (node (ref "J9") (pin "16") (pinfunction "16_16") (pintype "passive"))
      (node (ref "U5") (pin "27") (pinfunction "PD7_27") (pintype "bidirectional"))
    )
    (net (code "60") (name "PE0_D11") (class "Default")
      (node (ref "J9") (pin "12") (pinfunction "12_12") (pintype "passive"))
      (node (ref "U5") (pin "30") (pinfunction "PE0_30") (pintype "bidirectional"))
    )
    (net (code "61") (name "PE1_D12") (class "Default")
      (node (ref "J9") (pin "13") (pinfunction "13_13") (pintype "passive"))
      (node (ref "U5") (pin "31") (pinfunction "PE1_31") (pintype "bidirectional"))
    )
    (net (code "62") (name "PE2_D13") (class "Default")
      (node (ref "J9") (pin "14") (pinfunction "14_14") (pintype "passive"))
      (node (ref "U5") (pin "32") (pinfunction "PE2_32") (pintype "bidirectional"))
    )
    (net (code "63") (name "PE3_D8") (class "Default")
      (node (ref "J9") (pin "9") (pinfunction "9_9") (pintype "passive"))
      (node (ref "U5") (pin "33") (pinfunction "PE3_33") (pintype "bidirectional"))
    )
    (net (code "64") (name "PF0_D37") (class "Default")
      (node (ref "U5") (pin "34") (pinfunction "PF0_34") (pintype "bidirectional"))
    )
    (net (code "65") (name "PF1_D38") (class "Default")
      (node (ref "U5") (pin "35") (pinfunction "PF1_35") (pintype "bidirectional"))
    )
    (net (code "66") (name "PF2_D35_A12") (class "Default")
      (node (ref "U5") (pin "36") (pinfunction "PF2_36") (pintype "bidirectional"))
      (node (ref "U6") (pin "5") (pinfunction "2A_5") (pintype "bidirectional"))
    )
    (net (code "67") (name "PF3_D36_A13") (class "Default")
      (node (ref "Q1") (pin "3") (pinfunction "D_3") (pintype "passive"))
      (node (ref "R4") (pin "6") (pinfunction "2_6") (pintype "passive"))
      (node (ref "U5") (pin "37") (pinfunction "PF3_37") (pintype "bidirectional"))
    )
    (net (code "68") (name "PF4_D6~{}") (class "Default")
      (node (ref "J9") (pin "7") (pinfunction "7_7") (pintype "passive"))
      (node (ref "U5") (pin "38") (pinfunction "PF4_38") (pintype "bidirectional"))
    )
    (net (code "69") (name "PF5_D3~{}") (class "Default")
      (node (ref "J9") (pin "4") (pinfunction "4_4") (pintype "passive"))
      (node (ref "U5") (pin "39") (pinfunction "PF5_39") (pintype "bidirectional"))
    )
    (net (code "70") (name "PF6_RST") (class "Default")
      (node (ref "J6") (pin "3") (pinfunction "3_3") (pintype "passive"))
      (node (ref "R13") (pin "1") (pinfunction "1_1") (pintype "passive"))
      (node (ref "SW1") (pin "2") (pinfunction "2_2") (pintype "bidirectional"))
      (node (ref "U5") (pin "40") (pinfunction "PF6_40") (pintype "bidirectional"))
    )
    (net (code "71") (name "RED") (class "Default")
      (node (ref "D1") (pin "5") (pinfunction "RED-A_5") (pintype "bidirectional"))
      (node (ref "R11") (pin "2") (pinfunction "2_2") (pintype "passive"))
    )
    (net (code "72") (name "RESETN") (class "Default")
      (node (ref "J9") (pin "19") (pinfunction "19_19") (pintype "passive"))
      (node (ref "R3") (pin "2") (pinfunction "1_2") (pintype "passive"))
      (node (ref "U4") (pin "11") (pinfunction "PA28/RESETN_11") (pintype "input"))
    )
    (net (code "73") (name "RX_D11") (class "Default")
      (node (ref "Q3") (pin "4") (pinfunction "S_4") (pintype "passive"))
      (node (ref "R3") (pin "3") (pinfunction "1_3") (pintype "passive"))
      (node (ref "U4") (pin "10") (pinfunction "PA23_10") (pintype "bidirectional"))
    )
    (net (code "74") (name "SWCLK") (class "Default")
      (node (ref "J6") (pin "2") (pinfunction "2_2") (pintype "passive"))
      (node (ref "R3") (pin "1") (pinfunction "1_1") (pintype "passive"))
      (node (ref "U4") (pin "12") (pinfunction "PA30/SWCLK_12") (pintype "bidirectional"))
    )
    (net (code "75") (name "SWDIO") (class "Default")
      (node (ref "J6") (pin "1") (pinfunction "1_1") (pintype "passive"))
      (node (ref "U4") (pin "13") (pinfunction "PA31/SWDIO_13") (pintype "bidirectional"))
    )
    (net (code "76") (name "TX_D11") (class "Default")
      (node (ref "Q3") (pin "1") (pinfunction "S_1") (pintype "passive"))
      (node (ref "R5") (pin "2") (pinfunction "1_2") (pintype "passive"))
      (node (ref "U4") (pin "9") (pinfunction "PA22_9") (pintype "bidirectional"))
    )
    (net (code "77") (name "UPDI_5V") (class "Default")
      (node (ref "Q2") (pin "6") (pinfunction "D_6") (pintype "passive"))
      (node (ref "R5") (pin "3") (pinfunction "1_3") (pintype "passive"))
      (node (ref "U5") (pin "41") (pinfunction "UPDI_41") (pintype "bidirectional"))
    )
    (net (code "78") (name "V_USB") (class "Default")
      (node (ref "F1") (pin "1") (pinfunction "1_1") (pintype "bidirectional"))
      (node (ref "J5") (pin "A4B9") (pinfunction "VBUS_A4B9") (pintype "power_in"))
      (node (ref "J5") (pin "B4A9") (pinfunction "VBUS_B4A9") (pintype "power_in"))
      (node (ref "TVS1") (pin "5") (pinfunction "VCC_5") (pintype "power_in"))
    )
    (net (code "79") (name "unconnected-(B1-*D3-PadD3)") (class "Default")
      (node (ref "B1") (pin "D3") (pinfunction "*D3_D3") (pintype "bidirectional"))
    )
    (net (code "80") (name "unconnected-(B1-*D5-PadD5)") (class "Default")
      (node (ref "B1") (pin "D5") (pinfunction "*D5_D5") (pintype "bidirectional"))
    )
    (net (code "81") (name "unconnected-(B1-*D6-PadD6)") (class "Default")
      (node (ref "B1") (pin "D6") (pinfunction "*D6_D6") (pintype "bidirectional"))
    )
    (net (code "82") (name "unconnected-(B1-*D9-PadD9)") (class "Default")
      (node (ref "B1") (pin "D9") (pinfunction "*D9_D9") (pintype "bidirectional"))
    )
    (net (code "83") (name "unconnected-(B1-*D10-PadD10)") (class "Default")
      (node (ref "B1") (pin "D10") (pinfunction "*D10_D10") (pintype "bidirectional"))
    )
    (net (code "84") (name "unconnected-(B1-*D11-PadD11)") (class "Default")
      (node (ref "B1") (pin "D11") (pinfunction "*D11_D11") (pintype "bidirectional"))
    )
    (net (code "85") (name "unconnected-(B1-GND-PadGND@1)") (class "Default")
      (node (ref "B1") (pin "GND@1") (pinfunction "GND_GND@1") (pintype "bidirectional"))
    )
    (net (code "86") (name "unconnected-(B1-GND-PadGND@2)") (class "Default")
      (node (ref "B1") (pin "GND@2") (pinfunction "GND_GND@2") (pintype "bidirectional"))
    )
    (net (code "87") (name "unconnected-(B1-GND-PadGND@3)") (class "Default")
      (node (ref "B1") (pin "GND@3") (pinfunction "GND_GND@3") (pintype "bidirectional"))
    )
    (net (code "88") (name "unconnected-(B1-GND-PadGND@4)") (class "Default")
      (node (ref "B1") (pin "GND@4") (pinfunction "GND_GND@4") (pintype "bidirectional"))
    )
    (net (code "89") (name "unconnected-(B1-Pad3.3V)") (class "Default")
      (node (ref "B1") (pin "3.3V") (pinfunction "3.3V_3.3V") (pintype "bidirectional"))
    )
    (net (code "90") (name "unconnected-(B1-Pad5V)") (class "Default")
      (node (ref "B1") (pin "5V") (pinfunction "5V_5V") (pintype "bidirectional"))
    )
    (net (code "91") (name "unconnected-(B1-PadA0)") (class "Default")
      (node (ref "B1") (pin "A0") (pinfunction "A0_A0") (pintype "bidirectional"))
    )
    (net (code "92") (name "unconnected-(B1-PadA1)") (class "Default")
      (node (ref "B1") (pin "A1") (pinfunction "A1_A1") (pintype "bidirectional"))
    )
    (net (code "93") (name "unconnected-(B1-PadA2)") (class "Default")
      (node (ref "B1") (pin "A2") (pinfunction "A2_A2") (pintype "bidirectional"))
    )
    (net (code "94") (name "unconnected-(B1-PadA3)") (class "Default")
      (node (ref "B1") (pin "A3") (pinfunction "A3_A3") (pintype "bidirectional"))
    )
    (net (code "95") (name "unconnected-(B1-PadA4)") (class "Default")
      (node (ref "B1") (pin "A4") (pinfunction "A4_A4") (pintype "bidirectional"))
    )
    (net (code "96") (name "unconnected-(B1-PadA5)") (class "Default")
      (node (ref "B1") (pin "A5") (pinfunction "A5_A5") (pintype "bidirectional"))
    )
    (net (code "97") (name "unconnected-(B1-PadAREF)") (class "Default")
      (node (ref "B1") (pin "AREF") (pinfunction "AREF_AREF") (pintype "bidirectional"))
    )
    (net (code "98") (name "unconnected-(B1-PadD0)") (class "Default")
      (node (ref "B1") (pin "D0") (pinfunction "D0_D0") (pintype "bidirectional"))
    )
    (net (code "99") (name "unconnected-(B1-PadD1)") (class "Default")
      (node (ref "B1") (pin "D1") (pinfunction "D1_D1") (pintype "bidirectional"))
    )
    (net (code "100") (name "unconnected-(B1-PadD2)") (class "Default")
      (node (ref "B1") (pin "D2") (pinfunction "D2_D2") (pintype "bidirectional"))
    )
    (net (code "101") (name "unconnected-(B1-PadD4)") (class "Default")
      (node (ref "B1") (pin "D4") (pinfunction "D4_D4") (pintype "bidirectional"))
    )
    (net (code "102") (name "unconnected-(B1-PadD7)") (class "Default")
      (node (ref "B1") (pin "D7") (pinfunction "D7_D7") (pintype "bidirectional"))
    )
    (net (code "103") (name "unconnected-(B1-PadD8)") (class "Default")
      (node (ref "B1") (pin "D8") (pinfunction "D8_D8") (pintype "bidirectional"))
    )
    (net (code "104") (name "unconnected-(B1-PadD12)") (class "Default")
      (node (ref "B1") (pin "D12") (pinfunction "D12_D12") (pintype "bidirectional"))
    )
    (net (code "105") (name "unconnected-(B1-PadD13)") (class "Default")
      (node (ref "B1") (pin "D13") (pinfunction "D13_D13") (pintype "bidirectional"))
    )
    (net (code "106") (name "unconnected-(B1-PadIOREF)") (class "Default")
      (node (ref "B1") (pin "IOREF") (pinfunction "IOREF_IOREF") (pintype "bidirectional"))
    )
    (net (code "107") (name "unconnected-(B1-PadMISO)") (class "Default")
      (node (ref "B1") (pin "MISO") (pinfunction "MISO_MISO") (pintype "bidirectional"))
    )
    (net (code "108") (name "unconnected-(B1-PadMOSI)") (class "Default")
      (node (ref "B1") (pin "MOSI") (pinfunction "MOSI_MOSI") (pintype "bidirectional"))
    )
    (net (code "109") (name "unconnected-(B1-PadSCK)") (class "Default")
      (node (ref "B1") (pin "SCK") (pinfunction "SCK_SCK") (pintype "bidirectional"))
    )
    (net (code "110") (name "unconnected-(B1-PadSCL)") (class "Default")
      (node (ref "B1") (pin "SCL") (pinfunction "SCL_SCL") (pintype "bidirectional"))
    )
    (net (code "111") (name "unconnected-(B1-PadSDA)") (class "Default")
      (node (ref "B1") (pin "SDA") (pinfunction "SDA_SDA") (pintype "bidirectional"))
    )
    (net (code "112") (name "unconnected-(B1-PadVCC)") (class "Default")
      (node (ref "B1") (pin "VCC") (pinfunction "VCC_VCC") (pintype "bidirectional"))
    )
    (net (code "113") (name "unconnected-(B1-PadVIN)") (class "Default")
      (node (ref "B1") (pin "VIN") (pinfunction "VIN_VIN") (pintype "bidirectional"))
    )
    (net (code "114") (name "unconnected-(B1-~{RESET}-PadRESET@1)") (class "Default")
      (node (ref "B1") (pin "RESET@1") (pinfunction "~{RESET}_RESET@1") (pintype "bidirectional"))
    )
    (net (code "115") (name "unconnected-(B1-~{RESET}-PadRESET@2)") (class "Default")
      (node (ref "B1") (pin "RESET@2") (pinfunction "~{RESET}_RESET@2") (pintype "bidirectional"))
    )
    (net (code "116") (name "unconnected-(J4-Pad1)") (class "Default")
      (node (ref "J4") (pin "1") (pinfunction "1_1") (pintype "passive"))
    )
    (net (code "117") (name "unconnected-(J4-Pad2)") (class "Default")
      (node (ref "J4") (pin "2") (pinfunction "2_2") (pintype "passive"))
    )
    (net (code "118") (name "unconnected-(J5-SBU1-PadA8)") (class "Default")
      (node (ref "J5") (pin "A8") (pinfunction "SBU1_A8") (pintype "bidirectional"))
    )
    (net (code "119") (name "unconnected-(J5-SBU2-PadB8)") (class "Default")
      (node (ref "J5") (pin "B8") (pinfunction "SBU2_B8") (pintype "bidirectional"))
    )
    (net (code "120") (name "unconnected-(TVS1-IO3-Pad4)") (class "Default")
      (node (ref "TVS1") (pin "4") (pinfunction "IO3_4") (pintype "passive"))
    )
    (net (code "121") (name "unconnected-(TVS1-IO4-Pad6)") (class "Default")
      (node (ref "TVS1") (pin "6") (pinfunction "IO4_6") (pintype "passive"))
    )
    (net (code "122") (name "unconnected-(U1-CLK-Pad20)") (class "Default")
      (node (ref "U1") (pin "20") (pinfunction "CLK_20") (pintype "bidirectional"))
    )
    (net (code "123") (name "unconnected-(U1-CMD-Pad19)") (class "Default")
      (node (ref "U1") (pin "19") (pinfunction "CMD_19") (pintype "bidirectional"))
    )
    (net (code "124") (name "unconnected-(U1-IO2-Pad24)") (class "Default")
      (node (ref "U1") (pin "24") (pinfunction "IO2_24") (pintype "bidirectional"))
    )
    (net (code "125") (name "unconnected-(U1-IO4-Pad26)") (class "Default")
      (node (ref "U1") (pin "26") (pinfunction "IO4_26") (pintype "bidirectional"))
    )
    (net (code "126") (name "unconnected-(U1-IO12-Pad14)") (class "Default")
      (node (ref "U1") (pin "14") (pinfunction "IO12_14") (pintype "bidirectional"))
    )
    (net (code "127") (name "unconnected-(U1-IO13-Pad16)") (class "Default")
      (node (ref "U1") (pin "16") (pinfunction "IO13_16") (pintype "bidirectional"))
    )
    (net (code "128") (name "unconnected-(U1-IO15-Pad23)") (class "Default")
      (node (ref "U1") (pin "23") (pinfunction "IO15_23") (pintype "bidirectional"))
    )
    (net (code "129") (name "unconnected-(U1-IO16-Pad27)") (class "Default")
      (node (ref "U1") (pin "27") (pinfunction "IO16_27") (pintype "bidirectional"))
    )
    (net (code "130") (name "unconnected-(U1-IO17-Pad28)") (class "Default")
      (node (ref "U1") (pin "28") (pinfunction "IO17_28") (pintype "bidirectional"))
    )
    (net (code "131") (name "unconnected-(U1-IO19-Pad31)") (class "Default")
      (node (ref "U1") (pin "31") (pinfunction "IO19_31") (pintype "bidirectional"))
    )
    (net (code "132") (name "unconnected-(U1-IO32-Pad8)") (class "Default")
      (node (ref "U1") (pin "8") (pinfunction "IO32_8") (pintype "bidirectional"))
    )
    (net (code "133") (name "unconnected-(U1-IO34-Pad6)") (class "Default")
      (node (ref "U1") (pin "6") (pinfunction "IO34_6") (pintype "bidirectional"))
    )
    (net (code "134") (name "unconnected-(U1-IO35-Pad7)") (class "Default")
      (node (ref "U1") (pin "7") (pinfunction "IO35_7") (pintype "bidirectional"))
    )
    (net (code "135") (name "unconnected-(U1-SD0-Pad21)") (class "Default")
      (node (ref "U1") (pin "21") (pinfunction "SD0_21") (pintype "bidirectional"))
    )
    (net (code "136") (name "unconnected-(U1-SD1-Pad22)") (class "Default")
      (node (ref "U1") (pin "22") (pinfunction "SD1_22") (pintype "bidirectional"))
    )
    (net (code "137") (name "unconnected-(U1-SD2-Pad17)") (class "Default")
      (node (ref "U1") (pin "17") (pinfunction "SD2_17") (pintype "bidirectional"))
    )
    (net (code "138") (name "unconnected-(U1-SD3-Pad18)") (class "Default")
      (node (ref "U1") (pin "18") (pinfunction "SD3_18") (pintype "bidirectional"))
    )
    (net (code "139") (name "unconnected-(U1-SVN-Pad5)") (class "Default")
      (node (ref "U1") (pin "5") (pinfunction "SVN_5") (pintype "bidirectional"))
    )
    (net (code "140") (name "unconnected-(U1-SVP-Pad4)") (class "Default")
      (node (ref "U1") (pin "4") (pinfunction "SVP_4") (pintype "bidirectional"))
    )
    (net (code "141") (name "unconnected-(U4-PA02-Pad18)") (class "Default")
      (node (ref "U4") (pin "18") (pinfunction "PA02_18") (pintype "bidirectional"))
    )
    (net (code "142") (name "unconnected-(U4-PA03-Pad19)") (class "Default")
      (node (ref "U4") (pin "19") (pinfunction "PA03_19") (pintype "bidirectional"))
    )
    (net (code "143") (name "unconnected-(U4-PA04-Pad20)") (class "Default")
      (node (ref "U4") (pin "20") (pinfunction "PA04_20") (pintype "bidirectional"))
    )
    (net (code "144") (name "unconnected-(U4-PA05-Pad1)") (class "Default")
      (node (ref "U4") (pin "1") (pinfunction "PA05_1") (pintype "bidirectional"))
    )
    (net (code "145") (name "unconnected-(U4-PA06-Pad2)") (class "Default")
      (node (ref "U4") (pin "2") (pinfunction "PA06_2") (pintype "bidirectional"))
    )
    (net (code "146") (name "unconnected-(U4-PA07-Pad3)") (class "Default")
      (node (ref "U4") (pin "3") (pinfunction "PA07_3") (pintype "bidirectional"))
    )
    (net (code "147") (name "unconnected-(U4-PA08{slash}XIN32-Pad4)") (class "Default")
      (node (ref "U4") (pin "4") (pinfunction "PA08/XIN32_4") (pintype "input"))
    )
    (net (code "148") (name "unconnected-(U4-PA09{slash}XOUT32-Pad5)") (class "Default")
      (node (ref "U4") (pin "5") (pinfunction "PA09/XOUT32_5") (pintype "input"))
    )
    (net (code "149") (name "unconnected-(U4-PA16-Pad8)") (class "Default")
      (node (ref "U4") (pin "8") (pinfunction "PA16_8") (pintype "bidirectional"))
    )
    (net (code "150") (name "unconnected-(U6-4A-Pad9)") (class "Default")
      (node (ref "U6") (pin "9") (pinfunction "4A_9") (pintype "bidirectional"))
    )
    (net (code "151") (name "unconnected-(U6-4Y-Pad10)") (class "Default")
      (node (ref "U6") (pin "10") (pinfunction "4Y_10") (pintype "bidirectional"))
    )
  )
)
